# battery.net
KiCad netlist of a schematic drawn in Altium Designer
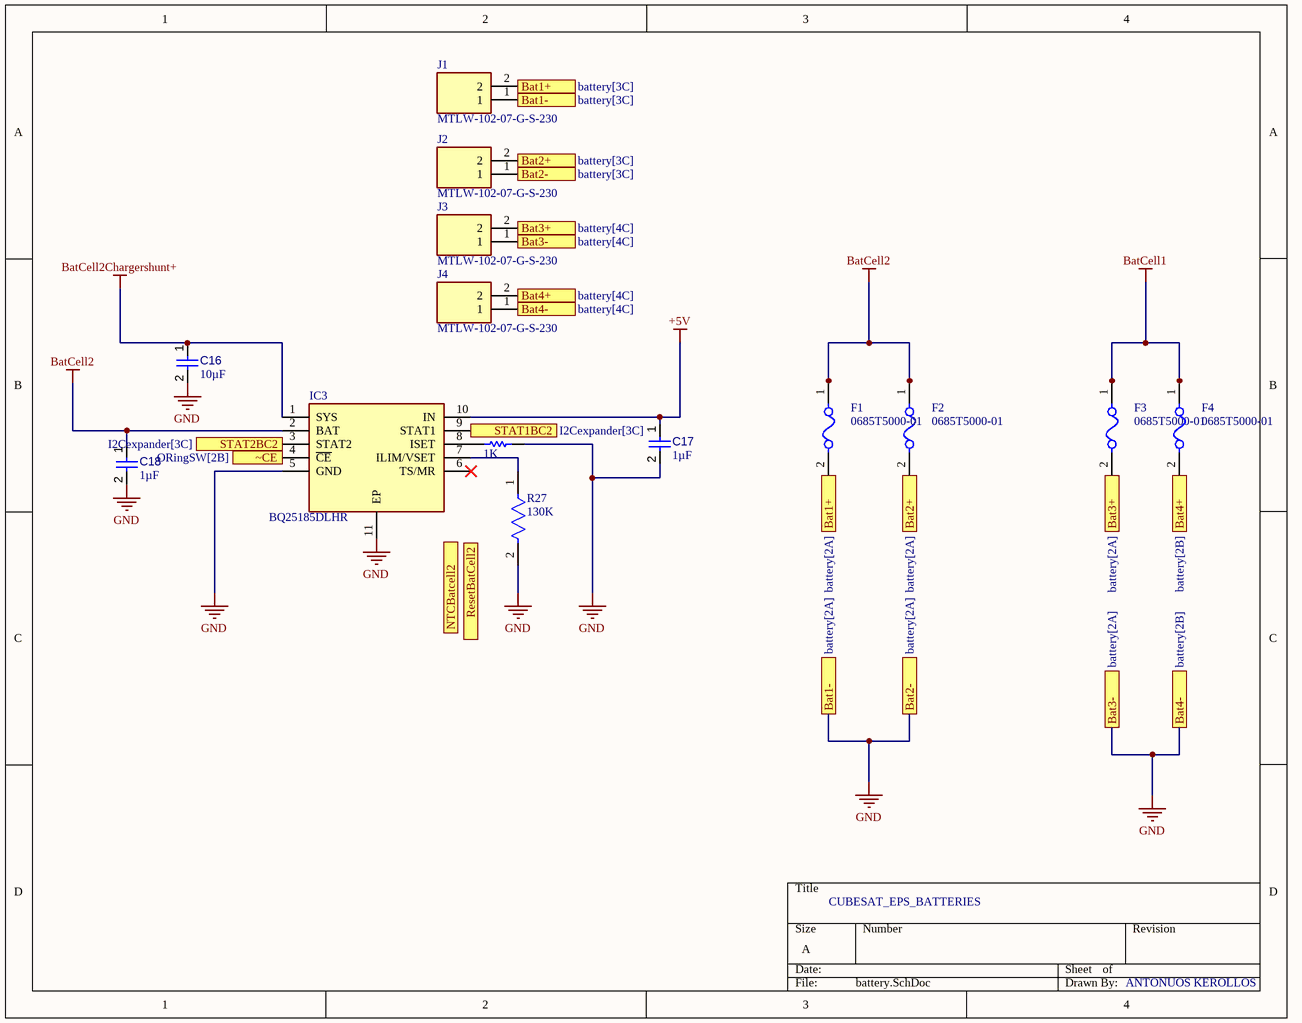
[diagram p0: battery.SchDoc]

(export (version "E")
  (design (tool "Eeschema 10.0.6"))
  (components
    (comp (ref "C16")
      (value "10µF")
      (footprint "CAPC0402(1005)60_L")
      (description "Chip Capacitor, 10µF +/-40%, 6.3V, 0402, Thickness 0.6 mm")
      (fields (field (name "TOLERANCE") "10%") (field (name "Comment") "Capacitor 10µF +/-40% 6.3V 0402"))
      (libsource (lib "ANTONUOS KEROLLOS") (part "CAP-NP-2"))
    )
    (comp (ref "C17")
      (value "1µF")
      (footprint "CAPC0402(1005)60_L")
      (description "Chip Capacitor, 1µF +/-20%, 10V, 0402, Thickness 0.6 mm")
      (fields (field (name "TOLERANCE") "10%") (field (name "Comment") "Capacitor 1µF +/-20% 10V 0402"))
      (libsource (lib "ANTONUOS KEROLLOS") (part "CAP-NP-2"))
    )
    (comp (ref "C18")
      (value "1µF")
      (footprint "CAPC0402(1005)60_L")
      (description "Chip Capacitor, 1µF +/-20%, 10V, 0402, Thickness 0.6 mm")
      (fields (field (name "TOLERANCE") "10%") (field (name "Comment") "Capacitor 1µF +/-20% 10V 0402"))
      (libsource (lib "ANTONUOS KEROLLOS") (part "CAP-NP-2"))
    )
    (comp (ref "F1")
      (value "0685T5000-01")
      (footprint "FP-0685T-MFG")
      (description "FUSE BOARD MNT 5A 63VAC/VDC 1206")
      (libsource (lib "Altium Content Vault") (part "5bcf9b9f640e542cf0359d10258e979"))
    )
    (comp (ref "F2")
      (value "0685T5000-01")
      (footprint "FP-0685T-MFG")
      (description "FUSE BOARD MNT 5A 63VAC/VDC 1206")
      (libsource (lib "Altium Content Vault") (part "5bcf9b9f640e542cf0359d10258e979"))
    )
    (comp (ref "F3")
      (value "0685T5000-01")
      (footprint "FP-0685T-MFG")
      (description "FUSE BOARD MNT 5A 63VAC/VDC 1206")
      (libsource (lib "Altium Content Vault") (part "5bcf9b9f640e542cf0359d10258e979"))
    )
    (comp (ref "F4")
      (value "0685T5000-01")
      (footprint "FP-0685T-MFG")
      (description "FUSE BOARD MNT 5A 63VAC/VDC 1206")
      (libsource (lib "Altium Content Vault") (part "5bcf9b9f640e542cf0359d10258e979"))
    )
    (comp (ref "IC3")
      (value "BQ25185DLHR")
      (footprint "SamacSys:SON40P220X200X80-11N")
      (description "Integrated Circuit")
      (fields (field (name "MOUSER PART NUMBER") "595-BQ25185DLHR"))
      (libsource (lib "*") (part "BQ25185DLHR"))
    )
    (comp (ref "J1")
      (value "MTLW-102-07-G-S-230")
      (footprint "SamacSys:HDRV2W82P0X254_1X2_508X249X876P")
      (description "Connector")
      (fields (field (name "MOUSER PART NUMBER") "200-MTLW10207GS230"))
      (libsource (lib "*") (part "MTLW-102-07-G-S-230"))
    )
    (comp (ref "J2")
      (value "MTLW-102-07-G-S-230")
      (footprint "SamacSys:HDRV2W82P0X254_1X2_508X249X876P")
      (description "Connector")
      (fields (field (name "MOUSER PART NUMBER") "200-MTLW10207GS230"))
      (libsource (lib "*") (part "MTLW-102-07-G-S-230"))
    )
    (comp (ref "J3")
      (value "MTLW-102-07-G-S-230")
      (footprint "SamacSys:HDRV2W82P0X254_1X2_508X249X876P")
      (description "Connector")
      (fields (field (name "MOUSER PART NUMBER") "200-MTLW10207GS230"))
      (libsource (lib "*") (part "MTLW-102-07-G-S-230"))
    )
    (comp (ref "J4")
      (value "MTLW-102-07-G-S-230")
      (footprint "SamacSys:HDRV2W82P0X254_1X2_508X249X876P")
      (description "Connector")
      (fields (field (name "MOUSER PART NUMBER") "200-MTLW10207GS230"))
      (libsource (lib "*") (part "MTLW-102-07-G-S-230"))
    )
    (comp (ref "R26")
      (value "1K")
      (footprint "RESC2013X60X35ML10T20")
      (description "Chip Resistor, 1 KOhm, +/- 1%, 125 mW, -55 to 155 degC, 0805 (2012 Metric), RoHS, Tape and Reel")
      (fields (field (name "TOLERANCE") "1%") (field (name "MANUFACTURER") "Yageo"))
      (libsource (lib "Altium Content Vault") (part "RES-2"))
    )
    (comp (ref "R27")
      (value "130K")
      (footprint "FP-CRCW0805-e3-IPC_C")
      (description "RES Thick Film, 130kΩ, 1%, 0.125W, 100ppm/°C, 0805")
      (fields (field (name "TOLERANCE") "1%"))
      (libsource (lib "Altium Content Vault") (part "1029c3af85768c4190bb7ad29bc67b5"))
    )
  )
  (nets
    (net (code "1") (name "+5V") (class "Default")
      (node (ref "C17") (pin "1") (pinfunction "1_1") (pintype "passive"))
      (node (ref "IC3") (pin "10") (pinfunction "IN_10") (pintype "passive"))
    )
    (net (code "2") (name "/Bat1+") (class "Default")
      (node (ref "F1") (pin "2") (pinfunction "2_2") (pintype "passive"))
      (node (ref "J1") (pin "2") (pinfunction "2_2") (pintype "passive"))
    )
    (net (code "3") (name "/Bat2+") (class "Default")
      (node (ref "F2") (pin "2") (pinfunction "2_2") (pintype "passive"))
      (node (ref "J2") (pin "2") (pinfunction "2_2") (pintype "passive"))
    )
    (net (code "4") (name "/Bat3+") (class "Default")
      (node (ref "F3") (pin "2") (pinfunction "2_2") (pintype "passive"))
      (node (ref "J3") (pin "2") (pinfunction "2_2") (pintype "passive"))
    )
    (net (code "5") (name "/Bat4+") (class "Default")
      (node (ref "F4") (pin "2") (pinfunction "2_2") (pintype "passive"))
      (node (ref "J4") (pin "2") (pinfunction "2_2") (pintype "passive"))
    )
    (net (code "8") (name "/STAT1BC2") (class "Default")
      (node (ref "IC3") (pin "9") (pinfunction "STAT1_9") (pintype "passive"))
    )
    (net (code "9") (name "/STAT2BC2") (class "Default")
      (node (ref "IC3") (pin "3") (pinfunction "STAT2_3") (pintype "passive"))
    )
    (net (code "10") (name "/~CE") (class "Default")
      (node (ref "IC3") (pin "4") (pinfunction "~{CE}_4") (pintype "passive"))
    )
    (net (code "11") (name "BatCell1") (class "Default")
      (node (ref "F3") (pin "1") (pinfunction "1_1") (pintype "passive"))
      (node (ref "F4") (pin "1") (pinfunction "1_1") (pintype "passive"))
    )
    (net (code "12") (name "BatCell2") (class "Default")
      (node (ref "C18") (pin "1") (pinfunction "1_1") (pintype "passive"))
      (node (ref "F1") (pin "1") (pinfunction "1_1") (pintype "passive"))
      (node (ref "F2") (pin "1") (pinfunction "1_1") (pintype "passive"))
      (node (ref "IC3") (pin "2") (pinfunction "BAT_2") (pintype "passive"))
    )
    (net (code "13") (name "BatCell2Chargershunt+") (class "Default")
      (node (ref "C16") (pin "1") (pinfunction "1_1") (pintype "passive"))
      (node (ref "IC3") (pin "1") (pinfunction "SYS_1") (pintype "passive"))
    )
    (net (code "14") (name "GND") (class "Default")
      (node (ref "C16") (pin "2") (pinfunction "2_2") (pintype "passive"))
      (node (ref "C17") (pin "2") (pinfunction "2_2") (pintype "passive"))
      (node (ref "C18") (pin "2") (pinfunction "2_2") (pintype "passive"))
      (node (ref "IC3") (pin "11") (pinfunction "EP_11") (pintype "passive"))
      (node (ref "IC3") (pin "5") (pinfunction "GND_5") (pintype "passive"))
      (node (ref "J1") (pin "1") (pinfunction "1_1") (pintype "passive"))
      (node (ref "J2") (pin "1") (pinfunction "1_1") (pintype "passive"))
      (node (ref "J3") (pin "1") (pinfunction "1_1") (pintype "passive"))
      (node (ref "J4") (pin "1") (pinfunction "1_1") (pintype "passive"))
      (node (ref "R26") (pin "1") (pinfunction "1_1") (pintype "passive"))
      (node (ref "R27") (pin "2") (pinfunction "2_2") (pintype "passive"))
    )
    (net (code "15") (name "Net-(IC3-ILIM{slash}VSET)") (class "Default")
      (node (ref "IC3") (pin "7") (pinfunction "ILIM/VSET_7") (pintype "passive"))
      (node (ref "R27") (pin "1") (pinfunction "1_1") (pintype "passive"))
    )
    (net (code "16") (name "Net-(IC3-ISET)") (class "Default")
      (node (ref "IC3") (pin "8") (pinfunction "ISET_8") (pintype "passive"))
      (node (ref "R26") (pin "2") (pinfunction "2_2") (pintype "passive"))
    )
    (net (code "17") (name "unconnected-(IC3-TS{slash}MR-Pad6)") (class "Default")
      (node (ref "IC3") (pin "6") (pinfunction "TS/MR_6") (pintype "passive+no_connect"))
    )
  )
)
